# PCB_12V5A_60Wascii_SchDoc_2022-06-16.net
KiCad netlist of a schematic drawn in Altium Designer
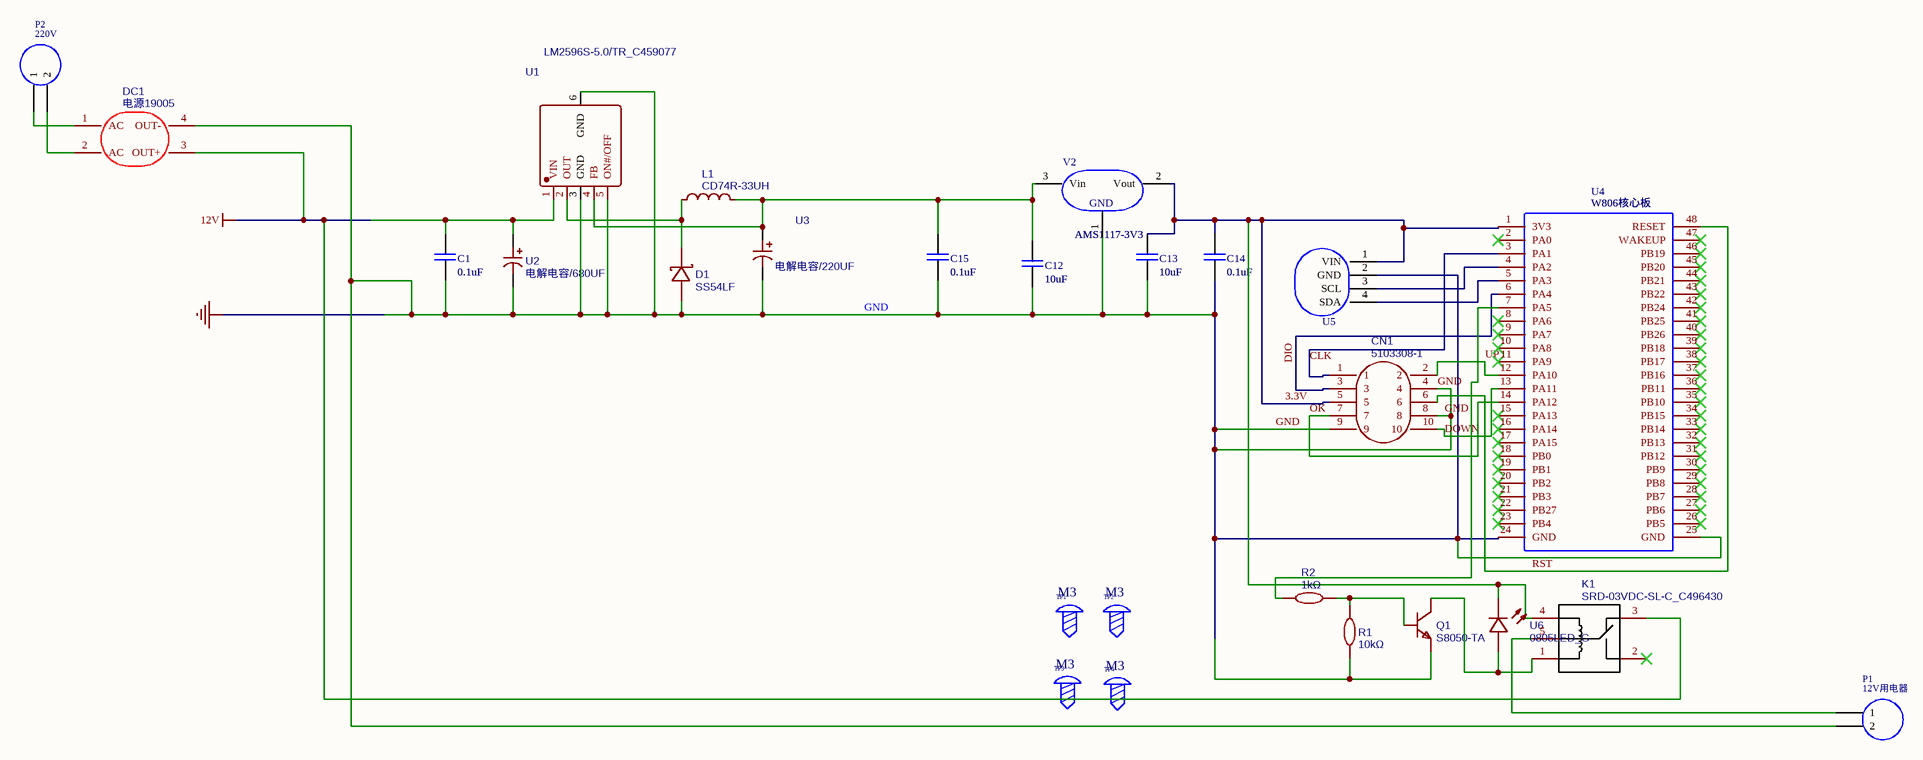
[diagram p0: PCB方案验证板  12V5A 60Wascii.SchDoc_2022-06-16.schdoc]

(export (version "E")
  (design (tool "Eeschema 10.0.6"))
  (components
    (comp (ref "C1") (value "0.1uF") (footprint "0805-C") (libsource (lib "") (part "root_1_0.1uF__1")))
    (comp (ref "C12")
      (value "10uF")
      (footprint "0805-C")
      (libsource (lib "altium-import") (part "root_1_10uF_"))
    )
    (comp (ref "C13")
      (value "10uF")
      (footprint "0805-C")
      (libsource (lib "altium-import") (part "root_1_10uF_"))
    )
    (comp (ref "C14")
      (value "0.1uF")
      (footprint "0805-C")
      (libsource (lib "altium-import") (part "root_1_0.1uF_"))
    )
    (comp (ref "C15") (value "0.1uF") (footprint "0805-C") (libsource (lib "") (part "root_1_0.1uF__1")))
    (comp (ref "CN1")
      (value "5103308-1")
      (footprint "IDC-TH_5103308-1")
      (fields (field (name "BOM_SUPPLIER PART") "C86466"))
      (libsource (lib "altium-import") (part "root_0_5103308-1_"))
    )
    (comp (ref "D1")
      (value "SS54LF")
      (footprint "SMAF_L3.5-W2.6-LS4.7-RD")
      (fields (field (name "BOM_SUPPLIER PART") "C128733") (field (name "CONTRIBUTOR") "LCSC"))
      (libsource (lib "altium-import") (part "root_3_SS54LF_"))
    )
    (comp (ref "DC1")
      (value "电源19005")
      (footprint "电源外购")
      (fields (field (name "BOM_SUPPLIER PART") "TB-zwd588888") (field (name "CONTRIBUTOR") "66ccff"))
      (libsource (lib "altium-import") (part "root_0_电源19005_"))
    )
    (comp (ref "K1")
      (value "SRD-03VDC-SL-C_C496430")
      (footprint "RELAY-TH_SRD-03VDC-SL-C")
      (fields
        (field (name "BOM_SUPPLIER PART") "C496430")
        (field (name "BOM_MANUFACTURER PART") "SRD-03VDC-SL-C")
        (field (name "CONTRIBUTOR") "LCSC")
      )
      (libsource (lib "altium-import") (part "root_0_SRD-03VDC-SL-C_C496430_"))
    )
    (comp (ref "L1")
      (value "CD74R-33UH")
      (footprint "IND-SMD_L7.3-W7.3")
      (fields
        (field (name "BOM_SUPPLIER PART") "C9900002925")
        (field (name "BOM_MANUFACTURER PART") "CD74R-33uH")
        (field (name "CONTRIBUTOR") "LCSC")
      )
      (libsource (lib "altium-import") (part "root_0_CD74R-33UH_"))
    )
    (comp (ref "P1")
      (value "12V用电器")
      (footprint "OUT")
      (fields (field (name "PUBLISHER") "Altium Limited"))
      (libsource (lib "altium-import") (part "root_0_12V用电器_"))
    )
    (comp (ref "P2")
      (value "220V")
      (footprint "OUT")
      (fields (field (name "PUBLISHER") "Altium Limited"))
      (libsource (lib "altium-import") (part "root_1_220V_"))
    )
    (comp (ref "Q1")
      (value "S8050-TA")
      (footprint "TO-92-3_L4.9-W3.7-P1.27-L")
      (fields (field (name "BOM_SUPPLIER PART") "C2910375") (field (name "CONTRIBUTOR") "LCSC"))
      (libsource (lib "altium-import") (part "root_0_S8050-TA_"))
    )
    (comp (ref "R1")
      (value "10kΩ")
      (footprint "R0805")
      (fields
        (field (name "BOM_SUPPLIER PART") "C267254")
        (field (name "BOM_MANUFACTURER PART") "R0805RXX332XJ08LTB")
        (field (name "CONTRIBUTOR") "LCSC")
      )
      (libsource (lib "altium-import") (part "root_1_10kΩ_"))
    )
    (comp (ref "R2")
      (value "1kΩ")
      (footprint "R0805")
      (fields
        (field (name "BOM_SUPPLIER PART") "C267254")
        (field (name "BOM_MANUFACTURER PART") "R0805RXX332XJ08LTB")
        (field (name "CONTRIBUTOR") "LCSC")
      )
      (libsource (lib "altium-import") (part "root_0_1kΩ_"))
    )
    (comp (ref "TP1") (value "NO") (footprint "M3X8+6_L") (libsource (lib "") (part "root_0_NO__1")))
    (comp (ref "TP2") (value "NO") (footprint "M3X8+6_L") (libsource (lib "") (part "root_0_NO__1")))
    (comp (ref "TP3")
      (value "NO")
      (footprint "M3X8+6_L")
      (libsource (lib "altium-import") (part "root_0_NO_"))
    )
    (comp (ref "TP4")
      (value "NO")
      (footprint "M3X8+6_L")
      (libsource (lib "altium-import") (part "root_0_NO_"))
    )
    (comp (ref "U1")
      (value "LM2596S-5.0/TR_C459077")
      (footprint "TO-263-5_L10.1-W8.7-P1.70-LS14.4-BR")
      (fields
        (field (name "BOM_SUPPLIER PART") "C459077")
        (field (name "BOM_MANUFACTURER PART") "LM2596S-5.0/TR")
        (field (name "CONTRIBUTOR") "LCSC")
      )
      (libsource (lib "altium-import") (part "root_1_LM2596S-5.0/TR_C459077_"))
    )
    (comp (ref "U2")
      (value "电解电容/680UF")
      (footprint "CAP-TH_BD10.0-P5.00-D0.6-FD")
      (fields
        (field (name "BOM_SUPPLIER PART") "C9900018858")
        (field (name "BOM_MANUFACTURER PART") "电解电容/22uF/450V/φ10*17-5.0")
        (field (name "CONTRIBUTOR") "lcsc")
      )
      (libsource (lib "altium-import") (part "root_3_电解电容/680UF_"))
    )
    (comp (ref "U3")
      (value "电解电容/220UF")
      (footprint "CAP-TH_BD10.0-P5.00-D0.6-FD")
      (fields
        (field (name "BOM_SUPPLIER PART") "C9900018858")
        (field (name "BOM_MANUFACTURER PART") "电解电容/22uF/450V/φ10*17-5.0")
        (field (name "CONTRIBUTOR") "lcsc")
      )
      (libsource (lib "altium-import") (part "root_3_电解电容/220UF_"))
    )
    (comp (ref "U4")
      (value "W806核心板")
      (footprint "W806最小系统")
      (libsource (lib "altium-import") (part "root_0_W806核心板_"))
    )
    (comp (ref "U5") (value "NO") (footprint "AHT10") (libsource (lib "") (part "root_0_NO__2")))
    (comp (ref "U6")
      (value "0805LED_G")
      (footprint "LED-SMD_L2.0-W1.3-R-RD")
      (fields (field (name "BOM_SUPPLIER PART") "C9900010436") (field (name "CONTRIBUTOR") "LCSC"))
      (libsource (lib "altium-import") (part "root_3_0805LED_G_"))
    )
    (comp (ref "V2")
      (value "AMS1117-3V3")
      (footprint "PG-SOT223-4_L6.5-W3.5-P2.30-LS7.0-BR")
      (libsource (lib "altium-import") (part "root_0_AMS1117-3V3_"))
    )
  )
  (nets
    (net (code "1") (name "/3.3V") (class "Default")
      (node (ref "C13") (pin "2") (pinfunction "2_2") (pintype "passive"))
      (node (ref "C14") (pin "2") (pinfunction "2_2") (pintype "passive"))
      (node (ref "CN1") (pin "5") (pinfunction "5_5") (pintype "passive"))
      (node (ref "K1") (pin "4") (pinfunction "4_4") (pintype "passive"))
      (node (ref "U4") (pin "1") (pinfunction "3V3_1") (pintype "passive"))
      (node (ref "U5") (pin "1") (pinfunction "VIN_1") (pintype "passive"))
      (node (ref "U6") (pin "2") (pinfunction "-_2") (pintype "passive"))
      (node (ref "V2") (pin "2") (pinfunction "Vout_2") (pintype "passive"))
    )
    (net (code "2") (name "/CLK") (class "Default")
      (node (ref "CN1") (pin "1") (pinfunction "1_1") (pintype "passive"))
      (node (ref "U4") (pin "3") (pinfunction "PA1_3") (pintype "passive"))
    )
    (net (code "3") (name "/DIO") (class "Default")
      (node (ref "CN1") (pin "3") (pinfunction "3_3") (pintype "passive"))
      (node (ref "U4") (pin "6") (pinfunction "PA4_6") (pintype "passive"))
    )
    (net (code "4") (name "/DOWN") (class "Default")
      (node (ref "CN1") (pin "10") (pinfunction "10_10") (pintype "passive"))
      (node (ref "U4") (pin "13") (pinfunction "PA11_13") (pintype "passive"))
    )
    (net (code "5") (name "/OK") (class "Default")
      (node (ref "CN1") (pin "7") (pinfunction "7_7") (pintype "passive"))
      (node (ref "U4") (pin "14") (pinfunction "PA12_14") (pintype "passive"))
    )
    (net (code "6") (name "/RST") (class "Default")
      (node (ref "CN1") (pin "6") (pinfunction "6_6") (pintype "passive"))
      (node (ref "U4") (pin "48") (pinfunction "RESET_48") (pintype "passive"))
    )
    (net (code "7") (name "/UP") (class "Default")
      (node (ref "CN1") (pin "2") (pinfunction "2_2") (pintype "passive"))
      (node (ref "U4") (pin "12") (pinfunction "PA10_12") (pintype "passive"))
    )
    (net (code "8") (name "12V") (class "Default")
      (node (ref "C1") (pin "2") (pinfunction "2_2") (pintype "passive"))
      (node (ref "DC1") (pin "3") (pinfunction "OUT+_3") (pintype "passive"))
      (node (ref "K1") (pin "3") (pinfunction "3_3") (pintype "passive"))
      (node (ref "U1") (pin "1") (pinfunction "VIN_1") (pintype "passive"))
      (node (ref "U2") (pin "1") (pinfunction "1_1") (pintype "passive"))
    )
    (net (code "9") (name "GND") (class "Default")
      (node (ref "C1") (pin "1") (pinfunction "1_1") (pintype "passive"))
      (node (ref "C12") (pin "1") (pinfunction "1_1") (pintype "passive"))
      (node (ref "C13") (pin "1") (pinfunction "1_1") (pintype "passive"))
      (node (ref "C14") (pin "1") (pinfunction "1_1") (pintype "passive"))
      (node (ref "C15") (pin "1") (pinfunction "1_1") (pintype "passive"))
      (node (ref "CN1") (pin "4") (pinfunction "4_4") (pintype "passive"))
      (node (ref "CN1") (pin "8") (pinfunction "8_8") (pintype "passive"))
      (node (ref "CN1") (pin "9") (pinfunction "9_9") (pintype "passive"))
      (node (ref "D1") (pin "2") (pinfunction "A_2") (pintype "passive"))
      (node (ref "DC1") (pin "4") (pinfunction "OUT-_4") (pintype "passive"))
      (node (ref "P1") (pin "GND") (pinfunction "2_GND") (pintype "passive"))
      (node (ref "Q1") (pin "1") (pinfunction "E_1") (pintype "passive"))
      (node (ref "R1") (pin "1") (pinfunction "1_1") (pintype "passive"))
      (node (ref "U1") (pin "3") (pinfunction "GND_3") (pintype "passive"))
      (node (ref "U1") (pin "5") (pinfunction "ON#/OFF_5") (pintype "passive"))
      (node (ref "U1") (pin "6") (pinfunction "GND_6") (pintype "passive"))
      (node (ref "U2") (pin "2") (pinfunction "2_2") (pintype "passive"))
      (node (ref "U3") (pin "2") (pinfunction "2_2") (pintype "passive"))
      (node (ref "U4") (pin "24") (pinfunction "GND_24") (pintype "passive"))
      (node (ref "U4") (pin "25") (pinfunction "GND_25") (pintype "passive"))
      (node (ref "U5") (pin "2") (pinfunction "GND_2") (pintype "passive"))
      (node (ref "V2") (pin "1") (pinfunction "GND_1") (pintype "passive"))
    )
    (net (code "10") (name "Net-(D1-C)") (class "Default")
      (node (ref "D1") (pin "1") (pinfunction "C_1") (pintype "passive"))
      (node (ref "L1") (pin "1") (pinfunction "1_1") (pintype "passive"))
      (node (ref "U1") (pin "2") (pinfunction "OUT_2") (pintype "passive"))
    )
    (net (code "11") (name "Net-(P1-1)") (class "Default")
      (node (ref "K1") (pin "5") (pinfunction "5_5") (pintype "passive"))
      (node (ref "P1") (pin "VCC") (pinfunction "1_VCC") (pintype "passive"))
    )
    (net (code "12") (name "Net-(P2-1)") (class "Default")
      (node (ref "DC1") (pin "1") (pinfunction "AC_1") (pintype "passive"))
      (node (ref "P2") (pin "VCC") (pinfunction "1_VCC") (pintype "passive"))
    )
    (net (code "13") (name "Net-(P2-2)") (class "Default")
      (node (ref "DC1") (pin "2") (pinfunction "AC_2") (pintype "passive"))
      (node (ref "P2") (pin "GND") (pinfunction "2_GND") (pintype "passive"))
    )
    (net (code "14") (name "Net-(Q1-B)") (class "Default")
      (node (ref "Q1") (pin "2") (pinfunction "B_2") (pintype "passive"))
      (node (ref "R1") (pin "2") (pinfunction "2_2") (pintype "passive"))
      (node (ref "R2") (pin "2") (pinfunction "2_2") (pintype "passive"))
    )
    (net (code "15") (name "Net-(Q1-C)") (class "Default")
      (node (ref "K1") (pin "1") (pinfunction "1_1") (pintype "passive"))
      (node (ref "Q1") (pin "3") (pinfunction "C_3") (pintype "passive"))
      (node (ref "U6") (pin "1") (pinfunction "+_1") (pintype "passive"))
    )
    (net (code "16") (name "Net-(U1-FB)") (class "Default")
      (node (ref "C12") (pin "2") (pinfunction "2_2") (pintype "passive"))
      (node (ref "C15") (pin "2") (pinfunction "2_2") (pintype "passive"))
      (node (ref "L1") (pin "2") (pinfunction "2_2") (pintype "passive"))
      (node (ref "U1") (pin "4") (pinfunction "FB_4") (pintype "passive"))
      (node (ref "U3") (pin "1") (pinfunction "1_1") (pintype "passive"))
      (node (ref "V2") (pin "3") (pinfunction "Vin_3") (pintype "passive"))
    )
    (net (code "17") (name "Net-(U4-PA2)") (class "Default")
      (node (ref "U4") (pin "4") (pinfunction "PA2_4") (pintype "passive"))
      (node (ref "U5") (pin "3") (pinfunction "SCL_3") (pintype "passive"))
    )
    (net (code "18") (name "Net-(U4-PA3)") (class "Default")
      (node (ref "U4") (pin "5") (pinfunction "PA3_5") (pintype "passive"))
      (node (ref "U5") (pin "4") (pinfunction "SDA_4") (pintype "passive"))
    )
    (net (code "19") (name "Net-(U4-PA5)") (class "Default")
      (node (ref "R2") (pin "1") (pinfunction "1_1") (pintype "passive"))
      (node (ref "U4") (pin "7") (pinfunction "PA5_7") (pintype "passive"))
    )
    (net (code "20") (name "unconnected-(K1-Pad2)") (class "Default")
      (node (ref "K1") (pin "2") (pinfunction "2_2") (pintype "passive+no_connect"))
    )
    (net (code "21") (name "unconnected-(U4-PA0-Pad2)") (class "Default")
      (node (ref "U4") (pin "2") (pinfunction "PA0_2") (pintype "passive+no_connect"))
    )
    (net (code "22") (name "unconnected-(U4-PA6-Pad8)") (class "Default")
      (node (ref "U4") (pin "8") (pinfunction "PA6_8") (pintype "passive+no_connect"))
    )
    (net (code "23") (name "unconnected-(U4-PA7-Pad9)") (class "Default")
      (node (ref "U4") (pin "9") (pinfunction "PA7_9") (pintype "passive+no_connect"))
    )
    (net (code "24") (name "unconnected-(U4-PA8-Pad10)") (class "Default")
      (node (ref "U4") (pin "10") (pinfunction "PA8_10") (pintype "passive+no_connect"))
    )
    (net (code "25") (name "unconnected-(U4-PA9-Pad11)") (class "Default")
      (node (ref "U4") (pin "11") (pinfunction "PA9_11") (pintype "passive+no_connect"))
    )
    (net (code "26") (name "unconnected-(U4-PA13-Pad15)") (class "Default")
      (node (ref "U4") (pin "15") (pinfunction "PA13_15") (pintype "passive+no_connect"))
    )
    (net (code "27") (name "unconnected-(U4-PA14-Pad16)") (class "Default")
      (node (ref "U4") (pin "16") (pinfunction "PA14_16") (pintype "passive+no_connect"))
    )
    (net (code "28") (name "unconnected-(U4-PA15-Pad17)") (class "Default")
      (node (ref "U4") (pin "17") (pinfunction "PA15_17") (pintype "passive+no_connect"))
    )
    (net (code "29") (name "unconnected-(U4-PB0-Pad18)") (class "Default")
      (node (ref "U4") (pin "18") (pinfunction "PB0_18") (pintype "passive+no_connect"))
    )
    (net (code "30") (name "unconnected-(U4-PB1-Pad19)") (class "Default")
      (node (ref "U4") (pin "19") (pinfunction "PB1_19") (pintype "passive+no_connect"))
    )
    (net (code "31") (name "unconnected-(U4-PB2-Pad20)") (class "Default")
      (node (ref "U4") (pin "20") (pinfunction "PB2_20") (pintype "passive+no_connect"))
    )
    (net (code "32") (name "unconnected-(U4-PB3-Pad21)") (class "Default")
      (node (ref "U4") (pin "21") (pinfunction "PB3_21") (pintype "passive+no_connect"))
    )
    (net (code "33") (name "unconnected-(U4-PB4-Pad23)") (class "Default")
      (node (ref "U4") (pin "23") (pinfunction "PB4_23") (pintype "passive+no_connect"))
    )
    (net (code "34") (name "unconnected-(U4-PB5-Pad26)") (class "Default")
      (node (ref "U4") (pin "26") (pinfunction "PB5_26") (pintype "passive+no_connect"))
    )
    (net (code "35") (name "unconnected-(U4-PB6-Pad27)") (class "Default")
      (node (ref "U4") (pin "27") (pinfunction "PB6_27") (pintype "passive+no_connect"))
    )
    (net (code "36") (name "unconnected-(U4-PB7-Pad28)") (class "Default")
      (node (ref "U4") (pin "28") (pinfunction "PB7_28") (pintype "passive+no_connect"))
    )
    (net (code "37") (name "unconnected-(U4-PB8-Pad29)") (class "Default")
      (node (ref "U4") (pin "29") (pinfunction "PB8_29") (pintype "passive+no_connect"))
    )
    (net (code "38") (name "unconnected-(U4-PB9-Pad30)") (class "Default")
      (node (ref "U4") (pin "30") (pinfunction "PB9_30") (pintype "passive+no_connect"))
    )
    (net (code "39") (name "unconnected-(U4-PB10-Pad35)") (class "Default")
      (node (ref "U4") (pin "35") (pinfunction "PB10_35") (pintype "passive+no_connect"))
    )
    (net (code "40") (name "unconnected-(U4-PB11-Pad36)") (class "Default")
      (node (ref "U4") (pin "36") (pinfunction "PB11_36") (pintype "passive+no_connect"))
    )
    (net (code "41") (name "unconnected-(U4-PB12-Pad31)") (class "Default")
      (node (ref "U4") (pin "31") (pinfunction "PB12_31") (pintype "passive+no_connect"))
    )
    (net (code "42") (name "unconnected-(U4-PB13-Pad32)") (class "Default")
      (node (ref "U4") (pin "32") (pinfunction "PB13_32") (pintype "passive+no_connect"))
    )
    (net (code "43") (name "unconnected-(U4-PB14-Pad33)") (class "Default")
      (node (ref "U4") (pin "33") (pinfunction "PB14_33") (pintype "passive+no_connect"))
    )
    (net (code "44") (name "unconnected-(U4-PB15-Pad34)") (class "Default")
      (node (ref "U4") (pin "34") (pinfunction "PB15_34") (pintype "passive+no_connect"))
    )
    (net (code "45") (name "unconnected-(U4-PB16-Pad37)") (class "Default")
      (node (ref "U4") (pin "37") (pinfunction "PB16_37") (pintype "passive+no_connect"))
    )
    (net (code "46") (name "unconnected-(U4-PB17-Pad38)") (class "Default")
      (node (ref "U4") (pin "38") (pinfunction "PB17_38") (pintype "passive+no_connect"))
    )
    (net (code "47") (name "unconnected-(U4-PB18-Pad39)") (class "Default")
      (node (ref "U4") (pin "39") (pinfunction "PB18_39") (pintype "passive+no_connect"))
    )
    (net (code "48") (name "unconnected-(U4-PB19-Pad46)") (class "Default")
      (node (ref "U4") (pin "46") (pinfunction "PB19_46") (pintype "passive+no_connect"))
    )
    (net (code "49") (name "unconnected-(U4-PB20-Pad45)") (class "Default")
      (node (ref "U4") (pin "45") (pinfunction "PB20_45") (pintype "passive+no_connect"))
    )
    (net (code "50") (name "unconnected-(U4-PB21-Pad44)") (class "Default")
      (node (ref "U4") (pin "44") (pinfunction "PB21_44") (pintype "passive+no_connect"))
    )
    (net (code "51") (name "unconnected-(U4-PB22-Pad43)") (class "Default")
      (node (ref "U4") (pin "43") (pinfunction "PB22_43") (pintype "passive+no_connect"))
    )
    (net (code "52") (name "unconnected-(U4-PB24-Pad42)") (class "Default")
      (node (ref "U4") (pin "42") (pinfunction "PB24_42") (pintype "passive+no_connect"))
    )
    (net (code "53") (name "unconnected-(U4-PB25-Pad41)") (class "Default")
      (node (ref "U4") (pin "41") (pinfunction "PB25_41") (pintype "passive+no_connect"))
    )
    (net (code "54") (name "unconnected-(U4-PB26-Pad40)") (class "Default")
      (node (ref "U4") (pin "40") (pinfunction "PB26_40") (pintype "passive+no_connect"))
    )
    (net (code "55") (name "unconnected-(U4-PB27-Pad22)") (class "Default")
      (node (ref "U4") (pin "22") (pinfunction "PB27_22") (pintype "passive+no_connect"))
    )
    (net (code "56") (name "unconnected-(U4-WAKEUP-Pad47)") (class "Default")
      (node (ref "U4") (pin "47") (pinfunction "WAKEUP_47") (pintype "passive+no_connect"))
    )
  )
)
